# AS3364_DG412_bus_mixer_v1_1.net
KiCad netlist of a schematic drawn in EAGLE
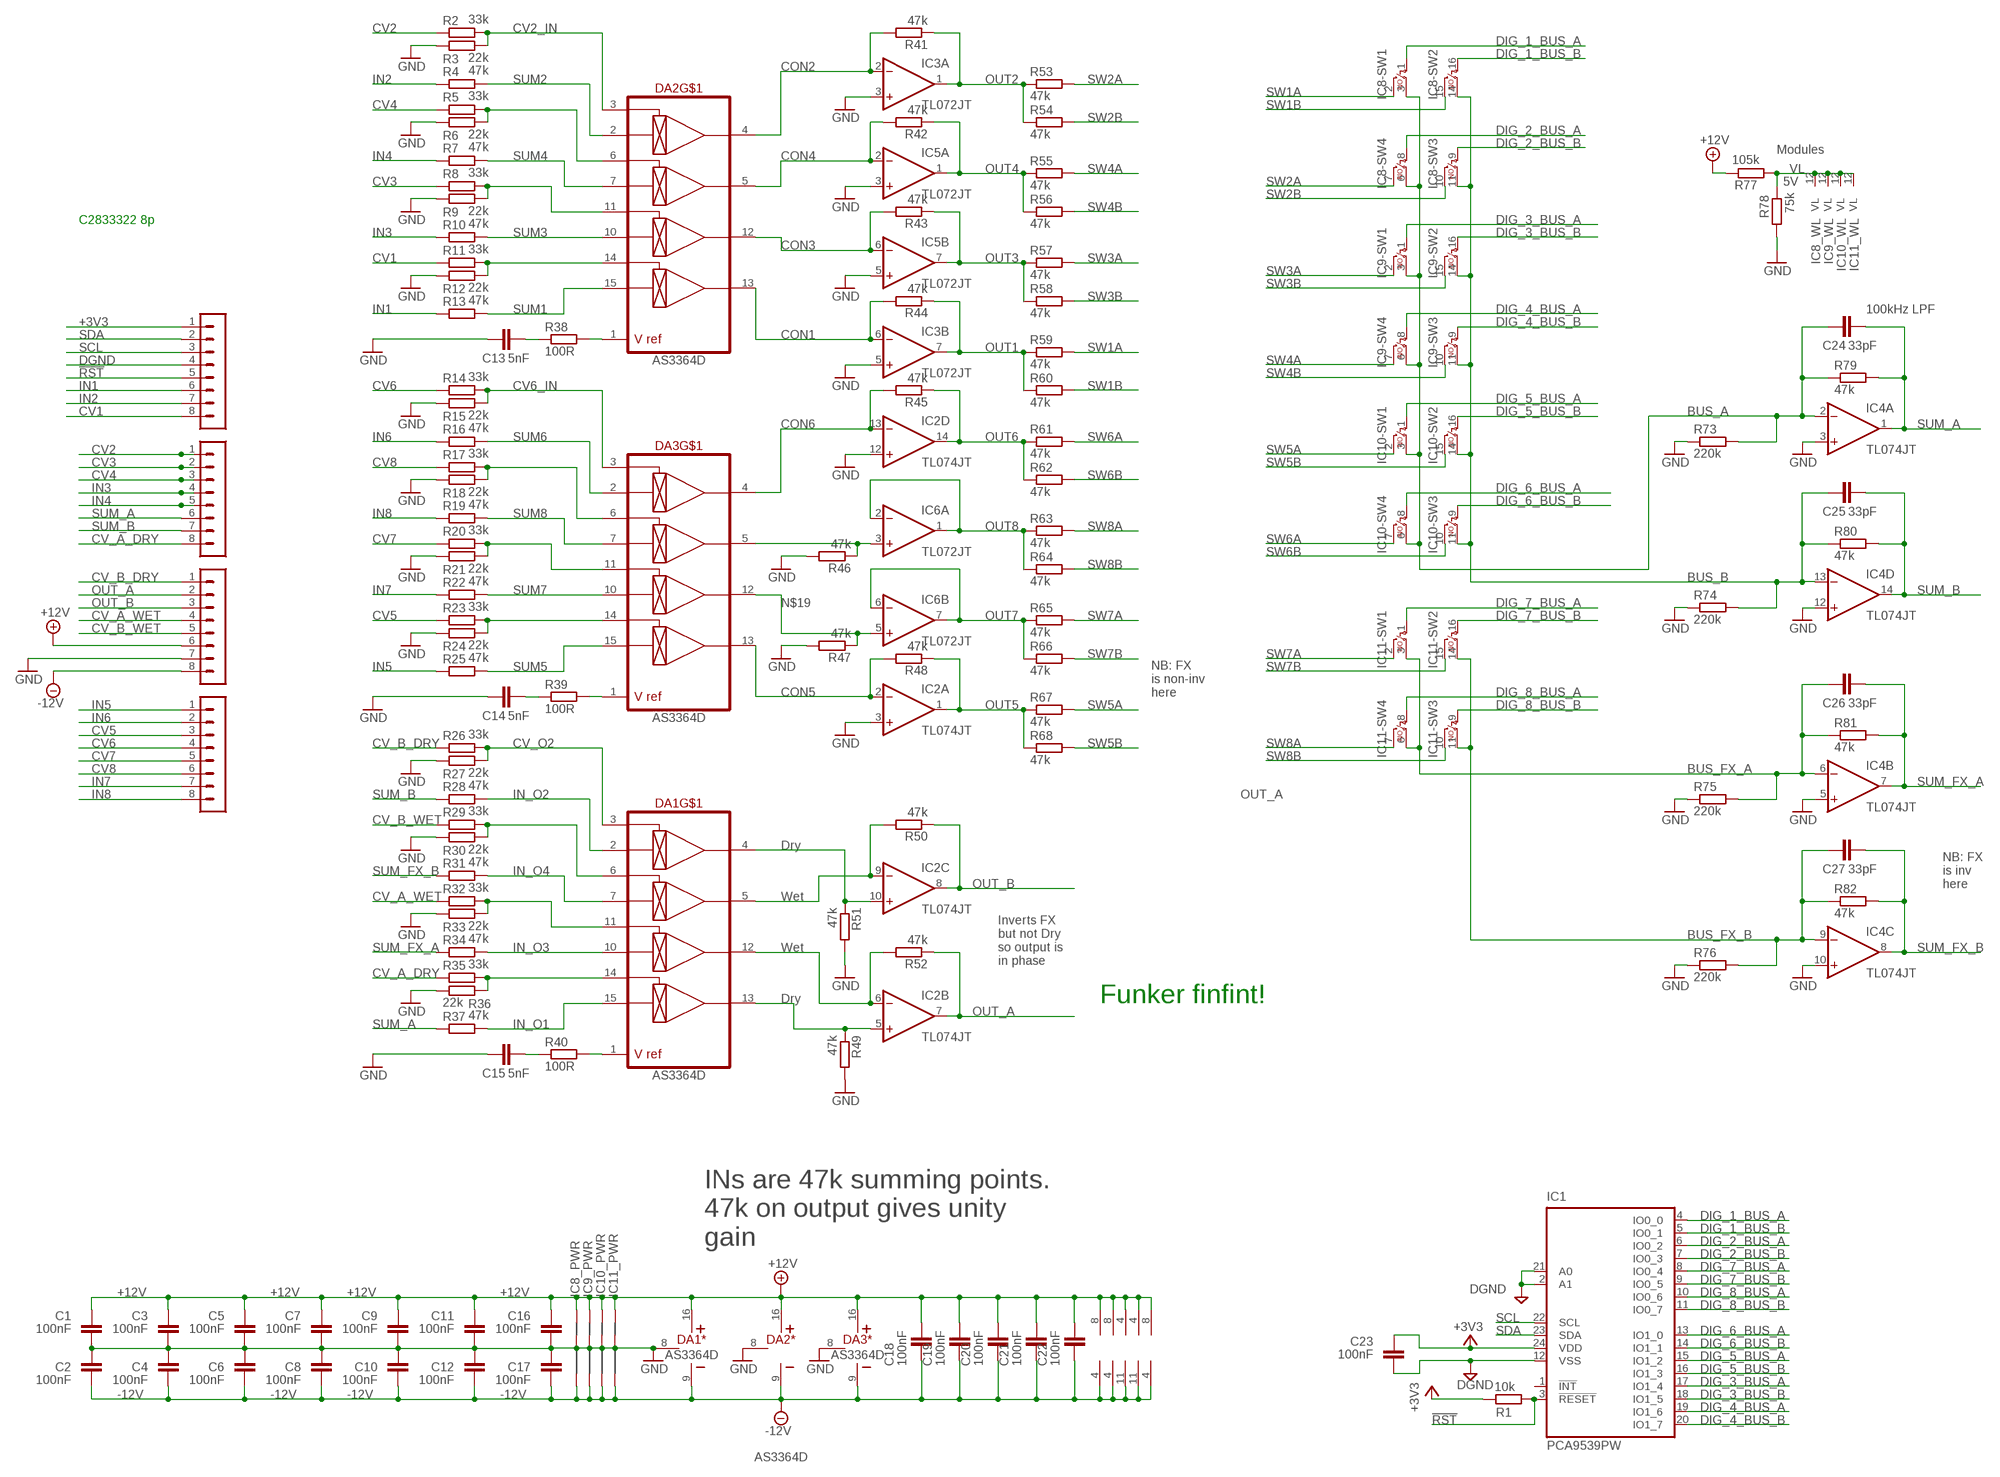
[diagram p0: schematic, sheet 1]

(export (version "E")
  (design (tool "Eeschema 10.0.6"))
  (components
    (comp (ref "C1")
      (value "100nF")
      (footprint "eagle-import:C0402")
      (libsource (lib "eagle-import") (part "C-EUC0402"))
    )
    (comp (ref "C2")
      (value "100nF")
      (footprint "eagle-import:C0402")
      (libsource (lib "eagle-import") (part "C-EUC0402"))
    )
    (comp (ref "C3")
      (value "100nF")
      (footprint "eagle-import:C0402")
      (libsource (lib "eagle-import") (part "C-EUC0402"))
    )
    (comp (ref "C4")
      (value "100nF")
      (footprint "eagle-import:C0402")
      (libsource (lib "eagle-import") (part "C-EUC0402"))
    )
    (comp (ref "C5")
      (value "100nF")
      (footprint "eagle-import:C0402")
      (libsource (lib "eagle-import") (part "C-EUC0402"))
    )
    (comp (ref "C6")
      (value "100nF")
      (footprint "eagle-import:C0402")
      (libsource (lib "eagle-import") (part "C-EUC0402"))
    )
    (comp (ref "C7")
      (value "100nF")
      (footprint "eagle-import:C0402")
      (libsource (lib "eagle-import") (part "C-EUC0402"))
    )
    (comp (ref "C8")
      (value "100nF")
      (footprint "eagle-import:C0402")
      (libsource (lib "eagle-import") (part "C-EUC0402"))
    )
    (comp (ref "C9")
      (value "100nF")
      (footprint "eagle-import:C0402")
      (libsource (lib "eagle-import") (part "C-EUC0402"))
    )
    (comp (ref "C10")
      (value "100nF")
      (footprint "eagle-import:C0402")
      (libsource (lib "eagle-import") (part "C-EUC0402"))
    )
    (comp (ref "C11")
      (value "100nF")
      (footprint "eagle-import:C0402")
      (libsource (lib "eagle-import") (part "C-EUC0402"))
    )
    (comp (ref "C12")
      (value "100nF")
      (footprint "eagle-import:C0402")
      (libsource (lib "eagle-import") (part "C-EUC0402"))
    )
    (comp (ref "C13")
      (value "5nF")
      (footprint "eagle-import:C0402-J")
      (libsource (lib "eagle-import") (part "C-EU-J"))
    )
    (comp (ref "C14")
      (value "5nF")
      (footprint "eagle-import:C0402-J")
      (libsource (lib "eagle-import") (part "C-EU-J"))
    )
    (comp (ref "C15")
      (value "5nF")
      (footprint "eagle-import:C0402-J")
      (libsource (lib "eagle-import") (part "C-EU-J"))
    )
    (comp (ref "C16")
      (value "100nF")
      (footprint "eagle-import:C0402")
      (libsource (lib "eagle-import") (part "C-EUC0402"))
    )
    (comp (ref "C17")
      (value "100nF")
      (footprint "eagle-import:C0402")
      (libsource (lib "eagle-import") (part "C-EUC0402"))
    )
    (comp (ref "C18")
      (value "100nF")
      (footprint "eagle-import:C0402")
      (libsource (lib "eagle-import") (part "C-EUC0402"))
    )
    (comp (ref "C19")
      (value "100nF")
      (footprint "eagle-import:C0402")
      (libsource (lib "eagle-import") (part "C-EUC0402"))
    )
    (comp (ref "C20")
      (value "100nF")
      (footprint "eagle-import:C0402")
      (libsource (lib "eagle-import") (part "C-EUC0402"))
    )
    (comp (ref "C21")
      (value "100nF")
      (footprint "eagle-import:C0402")
      (libsource (lib "eagle-import") (part "C-EUC0402"))
    )
    (comp (ref "C22")
      (value "100nF")
      (footprint "eagle-import:C0402")
      (libsource (lib "eagle-import") (part "C-EUC0402"))
    )
    (comp (ref "C23")
      (value "100nF")
      (footprint "eagle-import:C0402")
      (libsource (lib "eagle-import") (part "C-EUC0402"))
    )
    (comp (ref "C24")
      (value "33pF")
      (footprint "eagle-import:C0402-J")
      (libsource (lib "eagle-import") (part "C-EU-J"))
    )
    (comp (ref "C25")
      (value "33pF")
      (footprint "eagle-import:C0402-J")
      (libsource (lib "eagle-import") (part "C-EU-J"))
    )
    (comp (ref "C26")
      (value "33pF")
      (footprint "eagle-import:C0402-J")
      (libsource (lib "eagle-import") (part "C-EU-J"))
    )
    (comp (ref "C27")
      (value "33pF")
      (footprint "eagle-import:C0402-J")
      (libsource (lib "eagle-import") (part "C-EU-J"))
    )
    (comp (ref "DA1")
      (value "AS3364D")
      (footprint "eagle-import:DIL16J")
      (libsource (lib "eagle-import") (part "AS3364D"))
    )
    (comp (ref "DA2")
      (value "AS3364D")
      (footprint "eagle-import:DIL16J")
      (libsource (lib "eagle-import") (part "AS3364D"))
    )
    (comp (ref "DA3")
      (value "AS3364D")
      (footprint "eagle-import:DIL16J")
      (libsource (lib "eagle-import") (part "AS3364D"))
    )
    (comp (ref "IC1")
      (value "PCA9539PW")
      (footprint "eagle-import:TSSOP24J")
      (libsource (lib "eagle-import") (part "PCA9539PW"))
    )
    (comp (ref "IC2")
      (value "TL074JT")
      (footprint "eagle-import:TSSOP14J")
      (libsource (lib "eagle-import") (part "TL074JT"))
    )
    (comp (ref "IC3")
      (value "TL072JT")
      (footprint "eagle-import:TSSOP8J")
      (libsource (lib "eagle-import") (part "TL072JT"))
    )
    (comp (ref "IC4")
      (value "TL074JT")
      (footprint "eagle-import:TSSOP14J")
      (libsource (lib "eagle-import") (part "TL074JT"))
    )
    (comp (ref "IC5")
      (value "TL072JT")
      (footprint "eagle-import:TSSOP8J")
      (libsource (lib "eagle-import") (part "TL072JT"))
    )
    (comp (ref "IC6")
      (value "TL072JT")
      (footprint "eagle-import:TSSOP8J")
      (libsource (lib "eagle-import") (part "TL072JT"))
    )
    (comp (ref "IC8")
      (value "DG412-J")
      (footprint "eagle-import:DIL16J")
      (libsource (lib "eagle-import") (part "DG412-J"))
    )
    (comp (ref "IC9")
      (value "DG412-J")
      (footprint "eagle-import:DIL16J")
      (libsource (lib "eagle-import") (part "DG412-J"))
    )
    (comp (ref "IC10")
      (value "DG412-J")
      (footprint "eagle-import:DIL16J")
      (libsource (lib "eagle-import") (part "DG412-J"))
    )
    (comp (ref "IC11")
      (value "DG412-J")
      (footprint "eagle-import:DIL16J")
      (libsource (lib "eagle-import") (part "DG412-J"))
    )
    (comp (ref "R1")
      (value "10k")
      (footprint "eagle-import:R0402")
      (libsource (lib "eagle-import") (part "R-EU_R0402"))
    )
    (comp (ref "R2")
      (value "33k")
      (footprint "eagle-import:R0402")
      (libsource (lib "eagle-import") (part "R-EU_R0402"))
    )
    (comp (ref "R3")
      (value "22k")
      (footprint "eagle-import:R0402")
      (libsource (lib "eagle-import") (part "R-EU_R0402"))
    )
    (comp (ref "R4")
      (value "47k")
      (footprint "eagle-import:R0402")
      (libsource (lib "eagle-import") (part "R-EU_R0402"))
    )
    (comp (ref "R5")
      (value "33k")
      (footprint "eagle-import:R0402")
      (libsource (lib "eagle-import") (part "R-EU_R0402"))
    )
    (comp (ref "R6")
      (value "22k")
      (footprint "eagle-import:R0402")
      (libsource (lib "eagle-import") (part "R-EU_R0402"))
    )
    (comp (ref "R7")
      (value "47k")
      (footprint "eagle-import:R0402")
      (libsource (lib "eagle-import") (part "R-EU_R0402"))
    )
    (comp (ref "R8")
      (value "33k")
      (footprint "eagle-import:R0402")
      (libsource (lib "eagle-import") (part "R-EU_R0402"))
    )
    (comp (ref "R9")
      (value "22k")
      (footprint "eagle-import:R0402")
      (libsource (lib "eagle-import") (part "R-EU_R0402"))
    )
    (comp (ref "R10")
      (value "47k")
      (footprint "eagle-import:R0402")
      (libsource (lib "eagle-import") (part "R-EU_R0402"))
    )
    (comp (ref "R11")
      (value "33k")
      (footprint "eagle-import:R0402")
      (libsource (lib "eagle-import") (part "R-EU_R0402"))
    )
    (comp (ref "R12")
      (value "22k")
      (footprint "eagle-import:R0402")
      (libsource (lib "eagle-import") (part "R-EU_R0402"))
    )
    (comp (ref "R13")
      (value "47k")
      (footprint "eagle-import:R0402")
      (libsource (lib "eagle-import") (part "R-EU_R0402"))
    )
    (comp (ref "R14")
      (value "33k")
      (footprint "eagle-import:R0402")
      (libsource (lib "eagle-import") (part "R-EU_R0402"))
    )
    (comp (ref "R15")
      (value "22k")
      (footprint "eagle-import:R0402")
      (libsource (lib "eagle-import") (part "R-EU_R0402"))
    )
    (comp (ref "R16")
      (value "47k")
      (footprint "eagle-import:R0402")
      (libsource (lib "eagle-import") (part "R-EU_R0402"))
    )
    (comp (ref "R17")
      (value "33k")
      (footprint "eagle-import:R0402")
      (libsource (lib "eagle-import") (part "R-EU_R0402"))
    )
    (comp (ref "R18")
      (value "22k")
      (footprint "eagle-import:R0402")
      (libsource (lib "eagle-import") (part "R-EU_R0402"))
    )
    (comp (ref "R19")
      (value "47k")
      (footprint "eagle-import:R0402")
      (libsource (lib "eagle-import") (part "R-EU_R0402"))
    )
    (comp (ref "R20")
      (value "33k")
      (footprint "eagle-import:R0402")
      (libsource (lib "eagle-import") (part "R-EU_R0402"))
    )
    (comp (ref "R21")
      (value "22k")
      (footprint "eagle-import:R0402")
      (libsource (lib "eagle-import") (part "R-EU_R0402"))
    )
    (comp (ref "R22")
      (value "47k")
      (footprint "eagle-import:R0402")
      (libsource (lib "eagle-import") (part "R-EU_R0402"))
    )
    (comp (ref "R23")
      (value "33k")
      (footprint "eagle-import:R0402")
      (libsource (lib "eagle-import") (part "R-EU_R0402"))
    )
    (comp (ref "R24")
      (value "22k")
      (footprint "eagle-import:R0402")
      (libsource (lib "eagle-import") (part "R-EU_R0402"))
    )
    (comp (ref "R25")
      (value "47k")
      (footprint "eagle-import:R0402")
      (libsource (lib "eagle-import") (part "R-EU_R0402"))
    )
    (comp (ref "R26")
      (value "33k")
      (footprint "eagle-import:R0402")
      (libsource (lib "eagle-import") (part "R-EU_R0402"))
    )
    (comp (ref "R27")
      (value "22k")
      (footprint "eagle-import:R0402")
      (libsource (lib "eagle-import") (part "R-EU_R0402"))
    )
    (comp (ref "R28")
      (value "47k")
      (footprint "eagle-import:R0402")
      (libsource (lib "eagle-import") (part "R-EU_R0402"))
    )
    (comp (ref "R29")
      (value "33k")
      (footprint "eagle-import:R0402")
      (libsource (lib "eagle-import") (part "R-EU_R0402"))
    )
    (comp (ref "R30")
      (value "22k")
      (footprint "eagle-import:R0402")
      (libsource (lib "eagle-import") (part "R-EU_R0402"))
    )
    (comp (ref "R31")
      (value "47k")
      (footprint "eagle-import:R0402")
      (libsource (lib "eagle-import") (part "R-EU_R0402"))
    )
    (comp (ref "R32")
      (value "33k")
      (footprint "eagle-import:R0402")
      (libsource (lib "eagle-import") (part "R-EU_R0402"))
    )
    (comp (ref "R33")
      (value "22k")
      (footprint "eagle-import:R0402")
      (libsource (lib "eagle-import") (part "R-EU_R0402"))
    )
    (comp (ref "R34")
      (value "47k")
      (footprint "eagle-import:R0402")
      (libsource (lib "eagle-import") (part "R-EU_R0402"))
    )
    (comp (ref "R35")
      (value "33k")
      (footprint "eagle-import:R0402")
      (libsource (lib "eagle-import") (part "R-EU_R0402"))
    )
    (comp (ref "R36")
      (value "22k")
      (footprint "eagle-import:R0402")
      (libsource (lib "eagle-import") (part "R-EU_R0402"))
    )
    (comp (ref "R37")
      (value "47k")
      (footprint "eagle-import:R0402")
      (libsource (lib "eagle-import") (part "R-EU_R0402"))
    )
    (comp (ref "R38")
      (value "100R")
      (footprint "eagle-import:R0402")
      (libsource (lib "eagle-import") (part "R-EU_R0402"))
    )
    (comp (ref "R39")
      (value "100R")
      (footprint "eagle-import:R0402")
      (libsource (lib "eagle-import") (part "R-EU_R0402"))
    )
    (comp (ref "R40")
      (value "100R")
      (footprint "eagle-import:R0402")
      (libsource (lib "eagle-import") (part "R-EU_R0402"))
    )
    (comp (ref "R41")
      (value "47k")
      (footprint "eagle-import:R0402")
      (libsource (lib "eagle-import") (part "R-EU_R0402"))
    )
    (comp (ref "R42")
      (value "47k")
      (footprint "eagle-import:R0402")
      (libsource (lib "eagle-import") (part "R-EU_R0402"))
    )
    (comp (ref "R43")
      (value "47k")
      (footprint "eagle-import:R0402")
      (libsource (lib "eagle-import") (part "R-EU_R0402"))
    )
    (comp (ref "R44")
      (value "47k")
      (footprint "eagle-import:R0402")
      (libsource (lib "eagle-import") (part "R-EU_R0402"))
    )
    (comp (ref "R45")
      (value "47k")
      (footprint "eagle-import:R0402")
      (libsource (lib "eagle-import") (part "R-EU_R0402"))
    )
    (comp (ref "R46")
      (value "47k")
      (footprint "eagle-import:R0402")
      (libsource (lib "eagle-import") (part "R-EU_R0402"))
    )
    (comp (ref "R47")
      (value "47k")
      (footprint "eagle-import:R0402")
      (libsource (lib "eagle-import") (part "R-EU_R0402"))
    )
    (comp (ref "R48")
      (value "47k")
      (footprint "eagle-import:R0402")
      (libsource (lib "eagle-import") (part "R-EU_R0402"))
    )
    (comp (ref "R49")
      (value "47k")
      (footprint "eagle-import:R0402")
      (libsource (lib "eagle-import") (part "R-EU_R0402"))
    )
    (comp (ref "R50")
      (value "47k")
      (footprint "eagle-import:R0402")
      (libsource (lib "eagle-import") (part "R-EU_R0402"))
    )
    (comp (ref "R51")
      (value "47k")
      (footprint "eagle-import:R0402")
      (libsource (lib "eagle-import") (part "R-EU_R0402"))
    )
    (comp (ref "R52")
      (value "47k")
      (footprint "eagle-import:R0402")
      (libsource (lib "eagle-import") (part "R-EU_R0402"))
    )
    (comp (ref "R53")
      (value "47k")
      (footprint "eagle-import:R0402")
      (libsource (lib "eagle-import") (part "R-EU_R0402"))
    )
    (comp (ref "R54")
      (value "47k")
      (footprint "eagle-import:R0402")
      (libsource (lib "eagle-import") (part "R-EU_R0402"))
    )
    (comp (ref "R55")
      (value "47k")
      (footprint "eagle-import:R0402")
      (libsource (lib "eagle-import") (part "R-EU_R0402"))
    )
    (comp (ref "R56")
      (value "47k")
      (footprint "eagle-import:R0402")
      (libsource (lib "eagle-import") (part "R-EU_R0402"))
    )
    (comp (ref "R57")
      (value "47k")
      (footprint "eagle-import:R0402")
      (libsource (lib "eagle-import") (part "R-EU_R0402"))
    )
    (comp (ref "R58")
      (value "47k")
      (footprint "eagle-import:R0402")
      (libsource (lib "eagle-import") (part "R-EU_R0402"))
    )
    (comp (ref "R59")
      (value "47k")
      (footprint "eagle-import:R0402")
      (libsource (lib "eagle-import") (part "R-EU_R0402"))
    )
    (comp (ref "R60")
      (value "47k")
      (footprint "eagle-import:R0402")
      (libsource (lib "eagle-import") (part "R-EU_R0402"))
    )
    (comp (ref "R61")
      (value "47k")
      (footprint "eagle-import:R0402")
      (libsource (lib "eagle-import") (part "R-EU_R0402"))
    )
    (comp (ref "R62")
      (value "47k")
      (footprint "eagle-import:R0402")
      (libsource (lib "eagle-import") (part "R-EU_R0402"))
    )
    (comp (ref "R63")
      (value "47k")
      (footprint "eagle-import:R0402")
      (libsource (lib "eagle-import") (part "R-EU_R0402"))
    )
    (comp (ref "R64")
      (value "47k")
      (footprint "eagle-import:R0402")
      (libsource (lib "eagle-import") (part "R-EU_R0402"))
    )
    (comp (ref "R65")
      (value "47k")
      (footprint "eagle-import:R0402")
      (libsource (lib "eagle-import") (part "R-EU_R0402"))
    )
    (comp (ref "R66")
      (value "47k")
      (footprint "eagle-import:R0402")
      (libsource (lib "eagle-import") (part "R-EU_R0402"))
    )
    (comp (ref "R67")
      (value "47k")
      (footprint "eagle-import:R0402")
      (libsource (lib "eagle-import") (part "R-EU_R0402"))
    )
    (comp (ref "R68")
      (value "47k")
      (footprint "eagle-import:R0402")
      (libsource (lib "eagle-import") (part "R-EU_R0402"))
    )
    (comp (ref "R73")
      (value "220k")
      (footprint "eagle-import:R0402")
      (libsource (lib "eagle-import") (part "R-EU_R0402"))
    )
    (comp (ref "R74")
      (value "220k")
      (footprint "eagle-import:R0402")
      (libsource (lib "eagle-import") (part "R-EU_R0402"))
    )
    (comp (ref "R75")
      (value "220k")
      (footprint "eagle-import:R0402")
      (libsource (lib "eagle-import") (part "R-EU_R0402"))
    )
    (comp (ref "R76")
      (value "220k")
      (footprint "eagle-import:R0402")
      (libsource (lib "eagle-import") (part "R-EU_R0402"))
    )
    (comp (ref "R77")
      (value "105k")
      (footprint "eagle-import:R0402")
      (libsource (lib "eagle-import") (part "R-EU_R0402"))
    )
    (comp (ref "R78")
      (value "75k")
      (footprint "eagle-import:R0402")
      (libsource (lib "eagle-import") (part "R-EU_R0402"))
    )
    (comp (ref "R79")
      (value "47k")
      (footprint "eagle-import:R0402")
      (libsource (lib "eagle-import") (part "R-EU_R0402"))
    )
    (comp (ref "R80")
      (value "47k")
      (footprint "eagle-import:R0402")
      (libsource (lib "eagle-import") (part "R-EU_R0402"))
    )
    (comp (ref "R81")
      (value "47k")
      (footprint "eagle-import:R0402")
      (libsource (lib "eagle-import") (part "R-EU_R0402"))
    )
    (comp (ref "R82")
      (value "47k")
      (footprint "eagle-import:R0402")
      (libsource (lib "eagle-import") (part "R-EU_R0402"))
    )
    (comp (ref "SV1")
      (value "MA08-1JP")
      (footprint "eagle-import:SIP-PIN08-1J")
      (libsource (lib "eagle-import") (part "MA08-1JP"))
    )
    (comp (ref "SV3")
      (value "MA08-1JP")
      (footprint "eagle-import:SIP-PIN08-1J")
      (libsource (lib "eagle-import") (part "MA08-1JP"))
    )
    (comp (ref "SV4")
      (value "MA08-1JP")
      (footprint "eagle-import:SIP-PIN08-1J")
      (libsource (lib "eagle-import") (part "MA08-1JP"))
    )
    (comp (ref "SV33")
      (value "MA08-1JP")
      (footprint "eagle-import:SIP-PIN08-1J")
      (libsource (lib "eagle-import") (part "MA08-1JP"))
    )
  )
  (nets
    (net (code "1") (name "+3V3") (class "Default")
      (node (ref "C23") (pin "2") (pinfunction "2_2") (pintype "passive"))
      (node (ref "IC1") (pin "24") (pinfunction "VDD_24") (pintype "power_in"))
      (node (ref "R1") (pin "1") (pinfunction "1_1") (pintype "passive"))
      (node (ref "SV33") (pin "1") (pinfunction "1_1") (pintype "passive"))
    )
    (net (code "2") (name "+12V") (class "Default")
      (node (ref "C1") (pin "2") (pinfunction "2_2") (pintype "passive"))
      (node (ref "C11") (pin "2") (pinfunction "2_2") (pintype "passive"))
      (node (ref "C16") (pin "2") (pinfunction "2_2") (pintype "passive"))
      (node (ref "C18") (pin "2") (pinfunction "2_2") (pintype "passive"))
      (node (ref "C19") (pin "2") (pinfunction "2_2") (pintype "passive"))
      (node (ref "C20") (pin "2") (pinfunction "2_2") (pintype "passive"))
      (node (ref "C21") (pin "2") (pinfunction "2_2") (pintype "passive"))
      (node (ref "C22") (pin "2") (pinfunction "2_2") (pintype "passive"))
      (node (ref "C3") (pin "2") (pinfunction "2_2") (pintype "passive"))
      (node (ref "C5") (pin "2") (pinfunction "2_2") (pintype "passive"))
      (node (ref "C7") (pin "2") (pinfunction "2_2") (pintype "passive"))
      (node (ref "C9") (pin "2") (pinfunction "2_2") (pintype "passive"))
      (node (ref "DA1") (pin "16") (pinfunction "V+_16") (pintype "power_in"))
      (node (ref "DA2") (pin "16") (pinfunction "V+_16") (pintype "power_in"))
      (node (ref "DA3") (pin "16") (pinfunction "V+_16") (pintype "power_in"))
      (node (ref "IC10") (pin "13") (pinfunction "+15V_13") (pintype "power_in"))
      (node (ref "IC11") (pin "13") (pinfunction "+15V_13") (pintype "power_in"))
      (node (ref "IC2") (pin "4") (pinfunction "V+_4") (pintype "power_in"))
      (node (ref "IC3") (pin "8") (pinfunction "V+_8") (pintype "power_in"))
      (node (ref "IC4") (pin "4") (pinfunction "V+_4") (pintype "power_in"))
      (node (ref "IC5") (pin "8") (pinfunction "V+_8") (pintype "power_in"))
      (node (ref "IC6") (pin "8") (pinfunction "V+_8") (pintype "power_in"))
      (node (ref "IC8") (pin "13") (pinfunction "+15V_13") (pintype "power_in"))
      (node (ref "IC9") (pin "13") (pinfunction "+15V_13") (pintype "power_in"))
      (node (ref "R77") (pin "1") (pinfunction "1_1") (pintype "passive"))
      (node (ref "SV4") (pin "6") (pinfunction "6_6") (pintype "passive"))
    )
    (net (code "3") (name "-12V") (class "Default")
      (node (ref "C10") (pin "1") (pinfunction "1_1") (pintype "passive"))
      (node (ref "C12") (pin "1") (pinfunction "1_1") (pintype "passive"))
      (node (ref "C17") (pin "1") (pinfunction "1_1") (pintype "passive"))
      (node (ref "C18") (pin "1") (pinfunction "1_1") (pintype "passive"))
      (node (ref "C19") (pin "1") (pinfunction "1_1") (pintype "passive"))
      (node (ref "C2") (pin "1") (pinfunction "1_1") (pintype "passive"))
      (node (ref "C20") (pin "1") (pinfunction "1_1") (pintype "passive"))
      (node (ref "C21") (pin "1") (pinfunction "1_1") (pintype "passive"))
      (node (ref "C22") (pin "1") (pinfunction "1_1") (pintype "passive"))
      (node (ref "C4") (pin "1") (pinfunction "1_1") (pintype "passive"))
      (node (ref "C6") (pin "1") (pinfunction "1_1") (pintype "passive"))
      (node (ref "C8") (pin "1") (pinfunction "1_1") (pintype "passive"))
      (node (ref "DA1") (pin "9") (pinfunction "V-_9") (pintype "power_in"))
      (node (ref "DA2") (pin "9") (pinfunction "V-_9") (pintype "power_in"))
      (node (ref "DA3") (pin "9") (pinfunction "V-_9") (pintype "power_in"))
      (node (ref "IC10") (pin "4") (pinfunction "-15V_4") (pintype "power_in"))
      (node (ref "IC11") (pin "4") (pinfunction "-15V_4") (pintype "power_in"))
      (node (ref "IC2") (pin "11") (pinfunction "V-_11") (pintype "power_in"))
      (node (ref "IC3") (pin "4") (pinfunction "V-_4") (pintype "power_in"))
      (node (ref "IC4") (pin "11") (pinfunction "V-_11") (pintype "power_in"))
      (node (ref "IC5") (pin "4") (pinfunction "V-_4") (pintype "power_in"))
      (node (ref "IC6") (pin "4") (pinfunction "V-_4") (pintype "power_in"))
      (node (ref "IC8") (pin "4") (pinfunction "-15V_4") (pintype "power_in"))
      (node (ref "IC9") (pin "4") (pinfunction "-15V_4") (pintype "power_in"))
      (node (ref "SV4") (pin "8") (pinfunction "8_8") (pintype "passive"))
    )
    (net (code "4") (name "/BUS_A") (class "Default")
      (node (ref "C24") (pin "1") (pinfunction "1_1") (pintype "passive"))
      (node (ref "IC10") (pin "3") (pinfunction "S_3") (pintype "bidirectional"))
      (node (ref "IC10") (pin "6") (pinfunction "S_6") (pintype "bidirectional"))
      (node (ref "IC4") (pin "2") (pinfunction "-IN_2") (pintype "input"))
      (node (ref "IC8") (pin "3") (pinfunction "S_3") (pintype "bidirectional"))
      (node (ref "IC8") (pin "6") (pinfunction "S_6") (pintype "bidirectional"))
      (node (ref "IC9") (pin "3") (pinfunction "S_3") (pintype "bidirectional"))
      (node (ref "IC9") (pin "6") (pinfunction "S_6") (pintype "bidirectional"))
      (node (ref "R73") (pin "2") (pinfunction "2_2") (pintype "passive"))
      (node (ref "R79") (pin "1") (pinfunction "1_1") (pintype "passive"))
    )
    (net (code "5") (name "/BUS_B") (class "Default")
      (node (ref "C25") (pin "1") (pinfunction "1_1") (pintype "passive"))
      (node (ref "IC10") (pin "11") (pinfunction "S_11") (pintype "bidirectional"))
      (node (ref "IC10") (pin "14") (pinfunction "S_14") (pintype "bidirectional"))
      (node (ref "IC4") (pin "13") (pinfunction "-IN_13") (pintype "input"))
      (node (ref "IC8") (pin "11") (pinfunction "S_11") (pintype "bidirectional"))
      (node (ref "IC8") (pin "14") (pinfunction "S_14") (pintype "bidirectional"))
      (node (ref "IC9") (pin "11") (pinfunction "S_11") (pintype "bidirectional"))
      (node (ref "IC9") (pin "14") (pinfunction "S_14") (pintype "bidirectional"))
      (node (ref "R74") (pin "2") (pinfunction "2_2") (pintype "passive"))
      (node (ref "R80") (pin "1") (pinfunction "1_1") (pintype "passive"))
    )
    (net (code "6") (name "/BUS_FX_A") (class "Default")
      (node (ref "C26") (pin "1") (pinfunction "1_1") (pintype "passive"))
      (node (ref "IC11") (pin "3") (pinfunction "S_3") (pintype "bidirectional"))
      (node (ref "IC11") (pin "6") (pinfunction "S_6") (pintype "bidirectional"))
      (node (ref "IC4") (pin "6") (pinfunction "-IN_6") (pintype "input"))
      (node (ref "R75") (pin "2") (pinfunction "2_2") (pintype "passive"))
      (node (ref "R81") (pin "1") (pinfunction "1_1") (pintype "passive"))
    )
    (net (code "7") (name "/BUS_FX_B") (class "Default")
      (node (ref "C27") (pin "1") (pinfunction "1_1") (pintype "passive"))
      (node (ref "IC11") (pin "11") (pinfunction "S_11") (pintype "bidirectional"))
      (node (ref "IC11") (pin "14") (pinfunction "S_14") (pintype "bidirectional"))
      (node (ref "IC4") (pin "9") (pinfunction "-IN_9") (pintype "input"))
      (node (ref "R76") (pin "2") (pinfunction "2_2") (pintype "passive"))
      (node (ref "R82") (pin "1") (pinfunction "1_1") (pintype "passive"))
    )
    (net (code "8") (name "/CON1") (class "Default")
      (node (ref "DA2") (pin "13") (pinfunction "OUT4_13") (pintype "output"))
      (node (ref "IC3") (pin "6") (pinfunction "-IN_6") (pintype "input"))
      (node (ref "R44") (pin "2") (pinfunction "2_2") (pintype "passive"))
    )
    (net (code "9") (name "/CON2") (class "Default")
      (node (ref "DA2") (pin "4") (pinfunction "OUT1_4") (pintype "output"))
      (node (ref "IC3") (pin "2") (pinfunction "-IN_2") (pintype "input"))
      (node (ref "R41") (pin "2") (pinfunction "2_2") (pintype "passive"))
    )
    (net (code "10") (name "/CON3") (class "Default")
      (node (ref "DA2") (pin "12") (pinfunction "OUT3_12") (pintype "output"))
      (node (ref "IC5") (pin "6") (pinfunction "-IN_6") (pintype "input"))
      (node (ref "R43") (pin "2") (pinfunction "2_2") (pintype "passive"))
    )
    (net (code "11") (name "/CON4") (class "Default")
      (node (ref "DA2") (pin "5") (pinfunction "OUT2_5") (pintype "output"))
      (node (ref "IC5") (pin "2") (pinfunction "-IN_2") (pintype "input"))
      (node (ref "R42") (pin "2") (pinfunction "2_2") (pintype "passive"))
    )
    (net (code "12") (name "/CON5") (class "Default")
      (node (ref "DA3") (pin "13") (pinfunction "OUT4_13") (pintype "output"))
      (node (ref "IC2") (pin "2") (pinfunction "-IN_2") (pintype "input"))
      (node (ref "R48") (pin "2") (pinfunction "2_2") (pintype "passive"))
    )
    (net (code "13") (name "/CON6") (class "Default")
      (node (ref "DA3") (pin "4") (pinfunction "OUT1_4") (pintype "output"))
      (node (ref "IC2") (pin "13") (pinfunction "-IN_13") (pintype "input"))
      (node (ref "R45") (pin "2") (pinfunction "2_2") (pintype "passive"))
    )
    (net (code "14") (name "/CV1") (class "Default")
      (node (ref "R11") (pin "1") (pinfunction "1_1") (pintype "passive"))
      (node (ref "SV33") (pin "8") (pinfunction "8_8") (pintype "passive"))
    )
    (net (code "15") (name "/CV2") (class "Default")
      (node (ref "R2") (pin "1") (pinfunction "1_1") (pintype "passive"))
      (node (ref "SV1") (pin "1") (pinfunction "1_1") (pintype "passive"))
    )
    (net (code "16") (name "/CV2_IN") (class "Default")
      (node (ref "DA2") (pin "3") (pinfunction "CV1_3") (pintype "input"))
      (node (ref "R2") (pin "2") (pinfunction "2_2") (pintype "passive"))
      (node (ref "R3") (pin "2") (pinfunction "2_2") (pintype "passive"))
    )
    (net (code "17") (name "/CV3") (class "Default")
      (node (ref "R8") (pin "1") (pinfunction "1_1") (pintype "passive"))
      (node (ref "SV1") (pin "2") (pinfunction "2_2") (pintype "passive"))
    )
    (net (code "18") (name "/CV4") (class "Default")
      (node (ref "R5") (pin "1") (pinfunction "1_1") (pintype "passive"))
      (node (ref "SV1") (pin "3") (pinfunction "3_3") (pintype "passive"))
    )
    (net (code "19") (name "/CV5") (class "Default")
      (node (ref "R23") (pin "1") (pinfunction "1_1") (pintype "passive"))
      (node (ref "SV3") (pin "3") (pinfunction "3_3") (pintype "passive"))
    )
    (net (code "20") (name "/CV6") (class "Default")
      (node (ref "R14") (pin "1") (pinfunction "1_1") (pintype "passive"))
      (node (ref "SV3") (pin "4") (pinfunction "4_4") (pintype "passive"))
    )
    (net (code "21") (name "/CV6_IN") (class "Default")
      (node (ref "DA3") (pin "3") (pinfunction "CV1_3") (pintype "input"))
      (node (ref "R14") (pin "2") (pinfunction "2_2") (pintype "passive"))
      (node (ref "R15") (pin "2") (pinfunction "2_2") (pintype "passive"))
    )
    (net (code "22") (name "/CV7") (class "Default")
      (node (ref "R20") (pin "1") (pinfunction "1_1") (pintype "passive"))
      (node (ref "SV3") (pin "5") (pinfunction "5_5") (pintype "passive"))
    )
    (net (code "23") (name "/CV8") (class "Default")
      (node (ref "R17") (pin "1") (pinfunction "1_1") (pintype "passive"))
      (node (ref "SV3") (pin "6") (pinfunction "6_6") (pintype "passive"))
    )
    (net (code "24") (name "/CV_A_DRY") (class "Default")
      (node (ref "R35") (pin "1") (pinfunction "1_1") (pintype "passive"))
      (node (ref "SV1") (pin "8") (pinfunction "8_8") (pintype "passive"))
    )
    (net (code "25") (name "/CV_A_WET") (class "Default")
      (node (ref "R32") (pin "1") (pinfunction "1_1") (pintype "passive"))
      (node (ref "SV4") (pin "4") (pinfunction "4_4") (pintype "passive"))
    )
    (net (code "26") (name "/CV_B_DRY") (class "Default")
      (node (ref "R26") (pin "1") (pinfunction "1_1") (pintype "passive"))
      (node (ref "SV4") (pin "1") (pinfunction "1_1") (pintype "passive"))
    )
    (net (code "27") (name "/CV_B_WET") (class "Default")
      (node (ref "R29") (pin "1") (pinfunction "1_1") (pintype "passive"))
      (node (ref "SV4") (pin "5") (pinfunction "5_5") (pintype "passive"))
    )
    (net (code "28") (name "/CV_O2") (class "Default")
      (node (ref "DA1") (pin "3") (pinfunction "CV1_3") (pintype "input"))
      (node (ref "R26") (pin "2") (pinfunction "2_2") (pintype "passive"))
      (node (ref "R27") (pin "2") (pinfunction "2_2") (pintype "passive"))
    )
    (net (code "29") (name "/DIG_1_BUS_A") (class "Default")
      (node (ref "IC1") (pin "4") (pinfunction "IO0_0_4") (pintype "bidirectional"))
      (node (ref "IC8") (pin "1") (pinfunction "C_1") (pintype "bidirectional"))
    )
    (net (code "30") (name "/DIG_1_BUS_B") (class "Default")
      (node (ref "IC1") (pin "5") (pinfunction "IO0_1_5") (pintype "bidirectional"))
      (node (ref "IC8") (pin "16") (pinfunction "C_16") (pintype "bidirectional"))
    )
    (net (code "31") (name "/DIG_2_BUS_A") (class "Default")
      (node (ref "IC1") (pin "6") (pinfunction "IO0_2_6") (pintype "bidirectional"))
      (node (ref "IC8") (pin "8") (pinfunction "C_8") (pintype "bidirectional"))
    )
    (net (code "32") (name "/DIG_2_BUS_B") (class "Default")
      (node (ref "IC1") (pin "7") (pinfunction "IO0_3_7") (pintype "bidirectional"))
      (node (ref "IC8") (pin "9") (pinfunction "C_9") (pintype "bidirectional"))
    )
    (net (code "33") (name "/DIG_3_BUS_A") (class "Default")
      (node (ref "IC1") (pin "17") (pinfunction "IO1_4_17") (pintype "bidirectional"))
      (node (ref "IC9") (pin "1") (pinfunction "C_1") (pintype "bidirectional"))
    )
    (net (code "34") (name "/DIG_3_BUS_B") (class "Default")
      (node (ref "IC1") (pin "18") (pinfunction "IO1_5_18") (pintype "bidirectional"))
      (node (ref "IC9") (pin "16") (pinfunction "C_16") (pintype "bidirectional"))
    )
    (net (code "35") (name "/DIG_4_BUS_A") (class "Default")
      (node (ref "IC1") (pin "19") (pinfunction "IO1_6_19") (pintype "bidirectional"))
      (node (ref "IC9") (pin "8") (pinfunction "C_8") (pintype "bidirectional"))
    )
    (net (code "36") (name "/DIG_4_BUS_B") (class "Default")
      (node (ref "IC1") (pin "20") (pinfunction "IO1_7_20") (pintype "bidirectional"))
      (node (ref "IC9") (pin "9") (pinfunction "C_9") (pintype "bidirectional"))
    )
    (net (code "37") (name "/DIG_5_BUS_A") (class "Default")
      (node (ref "IC1") (pin "15") (pinfunction "IO1_2_15") (pintype "bidirectional"))
      (node (ref "IC10") (pin "1") (pinfunction "C_1") (pintype "bidirectional"))
    )
    (net (code "38") (name "/DIG_5_BUS_B") (class "Default")
      (node (ref "IC1") (pin "16") (pinfunction "IO1_3_16") (pintype "bidirectional"))
      (node (ref "IC10") (pin "16") (pinfunction "C_16") (pintype "bidirectional"))
    )
    (net (code "39") (name "/DIG_6_BUS_A") (class "Default")
      (node (ref "IC1") (pin "13") (pinfunction "IO1_0_13") (pintype "bidirectional"))
      (node (ref "IC10") (pin "8") (pinfunction "C_8") (pintype "bidirectional"))
    )
    (net (code "40") (name "/DIG_6_BUS_B") (class "Default")
      (node (ref "IC1") (pin "14") (pinfunction "IO1_1_14") (pintype "bidirectional"))
      (node (ref "IC10") (pin "9") (pinfunction "C_9") (pintype "bidirectional"))
    )
    (net (code "41") (name "/DIG_7_BUS_A") (class "Default")
      (node (ref "IC1") (pin "8") (pinfunction "IO0_4_8") (pintype "bidirectional"))
      (node (ref "IC11") (pin "1") (pinfunction "C_1") (pintype "bidirectional"))
    )
    (net (code "42") (name "/DIG_7_BUS_B") (class "Default")
      (node (ref "IC1") (pin "9") (pinfunction "IO0_5_9") (pintype "bidirectional"))
      (node (ref "IC11") (pin "16") (pinfunction "C_16") (pintype "bidirectional"))
    )
    (net (code "43") (name "/DIG_8_BUS_A") (class "Default")
      (node (ref "IC1") (pin "10") (pinfunction "IO0_6_10") (pintype "bidirectional"))
      (node (ref "IC11") (pin "8") (pinfunction "C_8") (pintype "bidirectional"))
    )
    (net (code "44") (name "/DIG_8_BUS_B") (class "Default")
      (node (ref "IC1") (pin "11") (pinfunction "IO0_7_11") (pintype "bidirectional"))
      (node (ref "IC11") (pin "9") (pinfunction "C_9") (pintype "bidirectional"))
    )
    (net (code "45") (name "/IN1") (class "Default")
      (node (ref "R13") (pin "1") (pinfunction "1_1") (pintype "passive"))
      (node (ref "SV33") (pin "6") (pinfunction "6_6") (pintype "passive"))
    )
    (net (code "46") (name "/IN2") (class "Default")
      (node (ref "R4") (pin "1") (pinfunction "1_1") (pintype "passive"))
      (node (ref "SV33") (pin "7") (pinfunction "7_7") (pintype "passive"))
    )
    (net (code "47") (name "/IN3") (class "Default")
      (node (ref "R10") (pin "1") (pinfunction "1_1") (pintype "passive"))
      (node (ref "SV1") (pin "4") (pinfunction "4_4") (pintype "passive"))
    )
    (net (code "48") (name "/IN4") (class "Default")
      (node (ref "R7") (pin "1") (pinfunction "1_1") (pintype "passive"))
      (node (ref "SV1") (pin "5") (pinfunction "5_5") (pintype "passive"))
    )
    (net (code "49") (name "/IN5") (class "Default")
      (node (ref "R25") (pin "1") (pinfunction "1_1") (pintype "passive"))
      (node (ref "SV3") (pin "1") (pinfunction "1_1") (pintype "passive"))
    )
    (net (code "50") (name "/IN6") (class "Default")
      (node (ref "R16") (pin "1") (pinfunction "1_1") (pintype "passive"))
      (node (ref "SV3") (pin "2") (pinfunction "2_2") (pintype "passive"))
    )
    (net (code "51") (name "/IN7") (class "Default")
      (node (ref "R22") (pin "1") (pinfunction "1_1") (pintype "passive"))
      (node (ref "SV3") (pin "7") (pinfunction "7_7") (pintype "passive"))
    )
    (net (code "52") (name "/IN8") (class "Default")
      (node (ref "R19") (pin "1") (pinfunction "1_1") (pintype "passive"))
      (node (ref "SV3") (pin "8") (pinfunction "8_8") (pintype "passive"))
    )
    (net (code "53") (name "/IN_O1") (class "Default")
      (node (ref "DA1") (pin "15") (pinfunction "IN4_15") (pintype "input"))
      (node (ref "R37") (pin "2") (pinfunction "2_2") (pintype "passive"))
    )
    (net (code "54") (name "/IN_O2") (class "Default")
      (node (ref "DA1") (pin "2") (pinfunction "IN1_2") (pintype "input"))
      (node (ref "R28") (pin "2") (pinfunction "2_2") (pintype "passive"))
    )
    (net (code "55") (name "/IN_O3") (class "Default")
      (node (ref "DA1") (pin "10") (pinfunction "IN3_10") (pintype "input"))
      (node (ref "R34") (pin "2") (pinfunction "2_2") (pintype "passive"))
    )
    (net (code "56") (name "/IN_O4") (class "Default")
      (node (ref "DA1") (pin "7") (pinfunction "IN2_7") (pintype "input"))
      (node (ref "R31") (pin "2") (pinfunction "2_2") (pintype "passive"))
    )
    (net (code "57") (name "/N$19") (class "Default")
      (node (ref "DA3") (pin "12") (pinfunction "OUT3_12") (pintype "output"))
      (node (ref "IC6") (pin "5") (pinfunction "+IN_5") (pintype "input"))
      (node (ref "R47") (pin "1") (pinfunction "1_1") (pintype "passive"))
    )
    (net (code "58") (name "/OUT1") (class "Default")
      (node (ref "IC3") (pin "7") (pinfunction "OUT_7") (pintype "output"))
      (node (ref "R44") (pin "1") (pinfunction "1_1") (pintype "passive"))
      (node (ref "R59") (pin "1") (pinfunction "1_1") (pintype "passive"))
      (node (ref "R60") (pin "1") (pinfunction "1_1") (pintype "passive"))
    )
    (net (code "59") (name "/OUT2") (class "Default")
      (node (ref "IC3") (pin "1") (pinfunction "OUT_1") (pintype "output"))
      (node (ref "R41") (pin "1") (pinfunction "1_1") (pintype "passive"))
      (node (ref "R53") (pin "1") (pinfunction "1_1") (pintype "passive"))
      (node (ref "R54") (pin "1") (pinfunction "1_1") (pintype "passive"))
    )
    (net (code "60") (name "/OUT3") (class "Default")
      (node (ref "IC5") (pin "7") (pinfunction "OUT_7") (pintype "output"))
      (node (ref "R43") (pin "1") (pinfunction "1_1") (pintype "passive"))
      (node (ref "R57") (pin "1") (pinfunction "1_1") (pintype "passive"))
      (node (ref "R58") (pin "1") (pinfunction "1_1") (pintype "passive"))
    )
    (net (code "61") (name "/OUT4") (class "Default")
      (node (ref "IC5") (pin "1") (pinfunction "OUT_1") (pintype "output"))
      (node (ref "R42") (pin "1") (pinfunction "1_1") (pintype "passive"))
      (node (ref "R55") (pin "1") (pinfunction "1_1") (pintype "passive"))
      (node (ref "R56") (pin "1") (pinfunction "1_1") (pintype "passive"))
    )
    (net (code "62") (name "/OUT5") (class "Default")
      (node (ref "IC2") (pin "1") (pinfunction "OUT_1") (pintype "output"))
      (node (ref "R48") (pin "1") (pinfunction "1_1") (pintype "passive"))
      (node (ref "R67") (pin "1") (pinfunction "1_1") (pintype "passive"))
      (node (ref "R68") (pin "1") (pinfunction "1_1") (pintype "passive"))
    )
    (net (code "63") (name "/OUT6") (class "Default")
      (node (ref "IC2") (pin "14") (pinfunction "OUT_14") (pintype "output"))
      (node (ref "R45") (pin "1") (pinfunction "1_1") (pintype "passive"))
      (node (ref "R61") (pin "1") (pinfunction "1_1") (pintype "passive"))
      (node (ref "R62") (pin "1") (pinfunction "1_1") (pintype "passive"))
    )
    (net (code "64") (name "/OUT7") (class "Default")
      (node (ref "IC6") (pin "6") (pinfunction "-IN_6") (pintype "input"))
      (node (ref "IC6") (pin "7") (pinfunction "OUT_7") (pintype "output"))
      (node (ref "R65") (pin "1") (pinfunction "1_1") (pintype "passive"))
      (node (ref "R66") (pin "1") (pinfunction "1_1") (pintype "passive"))
    )
    (net (code "65") (name "/OUT8") (class "Default")
      (node (ref "IC6") (pin "1") (pinfunction "OUT_1") (pintype "output"))
      (node (ref "IC6") (pin "2") (pinfunction "-IN_2") (pintype "input"))
      (node (ref "R63") (pin "1") (pinfunction "1_1") (pintype "passive"))
      (node (ref "R64") (pin "1") (pinfunction "1_1") (pintype "passive"))
    )
    (net (code "66") (name "/OUT_A") (class "Default")
      (node (ref "IC2") (pin "7") (pinfunction "OUT_7") (pintype "output"))
      (node (ref "R52") (pin "1") (pinfunction "1_1") (pintype "passive"))
      (node (ref "SV4") (pin "2") (pinfunction "2_2") (pintype "passive"))
    )
    (net (code "67") (name "/OUT_B") (class "Default")
      (node (ref "IC2") (pin "8") (pinfunction "OUT_8") (pintype "output"))
      (node (ref "R50") (pin "1") (pinfunction "1_1") (pintype "passive"))
      (node (ref "SV4") (pin "3") (pinfunction "3_3") (pintype "passive"))
    )
    (net (code "68") (name "/SCL") (class "Default")
      (node (ref "IC1") (pin "22") (pinfunction "SCL_22") (pintype "bidirectional"))
      (node (ref "SV33") (pin "3") (pinfunction "3_3") (pintype "passive"))
    )
    (net (code "69") (name "/SDA") (class "Default")
      (node (ref "IC1") (pin "23") (pinfunction "SDA_23") (pintype "bidirectional"))
      (node (ref "SV33") (pin "2") (pinfunction "2_2") (pintype "passive"))
    )
    (net (code "70") (name "/SUM1") (class "Default")
      (node (ref "DA2") (pin "15") (pinfunction "IN4_15") (pintype "input"))
      (node (ref "R13") (pin "2") (pinfunction "2_2") (pintype "passive"))
    )
    (net (code "71") (name "/SUM2") (class "Default")
      (node (ref "DA2") (pin "2") (pinfunction "IN1_2") (pintype "input"))
      (node (ref "R4") (pin "2") (pinfunction "2_2") (pintype "passive"))
    )
    (net (code "72") (name "/SUM3") (class "Default")
      (node (ref "DA2") (pin "10") (pinfunction "IN3_10") (pintype "input"))
      (node (ref "R10") (pin "2") (pinfunction "2_2") (pintype "passive"))
    )
    (net (code "73") (name "/SUM4") (class "Default")
      (node (ref "DA2") (pin "7") (pinfunction "IN2_7") (pintype "input"))
      (node (ref "R7") (pin "2") (pinfunction "2_2") (pintype "passive"))
    )
    (net (code "74") (name "/SUM5") (class "Default")
      (node (ref "DA3") (pin "15") (pinfunction "IN4_15") (pintype "input"))
      (node (ref "R25") (pin "2") (pinfunction "2_2") (pintype "passive"))
    )
    (net (code "75") (name "/SUM6") (class "Default")
      (node (ref "DA3") (pin "2") (pinfunction "IN1_2") (pintype "input"))
      (node (ref "R16") (pin "2") (pinfunction "2_2") (pintype "passive"))
    )
    (net (code "76") (name "/SUM7") (class "Default")
      (node (ref "DA3") (pin "10") (pinfunction "IN3_10") (pintype "input"))
      (node (ref "R22") (pin "2") (pinfunction "2_2") (pintype "passive"))
    )
    (net (code "77") (name "/SUM8") (class "Default")
      (node (ref "DA3") (pin "7") (pinfunction "IN2_7") (pintype "input"))
      (node (ref "R19") (pin "2") (pinfunction "2_2") (pintype "passive"))
    )
    (net (code "78") (name "/SUM_A") (class "Default")
      (node (ref "C24") (pin "2") (pinfunction "2_2") (pintype "passive"))
      (node (ref "IC4") (pin "1") (pinfunction "OUT_1") (pintype "output"))
      (node (ref "R37") (pin "1") (pinfunction "1_1") (pintype "passive"))
      (node (ref "R79") (pin "2") (pinfunction "2_2") (pintype "passive"))
      (node (ref "SV1") (pin "6") (pinfunction "6_6") (pintype "passive"))
    )
    (net (code "79") (name "/SUM_B") (class "Default")
      (node (ref "C25") (pin "2") (pinfunction "2_2") (pintype "passive"))
      (node (ref "IC4") (pin "14") (pinfunction "OUT_14") (pintype "output"))
      (node (ref "R28") (pin "1") (pinfunction "1_1") (pintype "passive"))
      (node (ref "R80") (pin "2") (pinfunction "2_2") (pintype "passive"))
      (node (ref "SV1") (pin "7") (pinfunction "7_7") (pintype "passive"))
    )
    (net (code "80") (name "/SUM_FX_A") (class "Default")
      (node (ref "C26") (pin "2") (pinfunction "2_2") (pintype "passive"))
      (node (ref "IC4") (pin "7") (pinfunction "OUT_7") (pintype "output"))
      (node (ref "R34") (pin "1") (pinfunction "1_1") (pintype "passive"))
      (node (ref "R81") (pin "2") (pinfunction "2_2") (pintype "passive"))
    )
    (net (code "81") (name "/SUM_FX_B") (class "Default")
      (node (ref "C27") (pin "2") (pinfunction "2_2") (pintype "passive"))
      (node (ref "IC4") (pin "8") (pinfunction "OUT_8") (pintype "output"))
      (node (ref "R31") (pin "1") (pinfunction "1_1") (pintype "passive"))
      (node (ref "R82") (pin "2") (pinfunction "2_2") (pintype "passive"))
    )
    (net (code "82") (name "/SW1A") (class "Default")
      (node (ref "IC8") (pin "2") (pinfunction "D_2") (pintype "bidirectional"))
      (node (ref "R59") (pin "2") (pinfunction "2_2") (pintype "passive"))
    )
    (net (code "83") (name "/SW1B") (class "Default")
      (node (ref "IC8") (pin "15") (pinfunction "D_15") (pintype "bidirectional"))
      (node (ref "R60") (pin "2") (pinfunction "2_2") (pintype "passive"))
    )
    (net (code "84") (name "/SW2A") (class "Default")
      (node (ref "IC8") (pin "7") (pinfunction "D_7") (pintype "bidirectional"))
      (node (ref "R53") (pin "2") (pinfunction "2_2") (pintype "passive"))
    )
    (net (code "85") (name "/SW2B") (class "Default")
      (node (ref "IC8") (pin "10") (pinfunction "D_10") (pintype "bidirectional"))
      (node (ref "R54") (pin "2") (pinfunction "2_2") (pintype "passive"))
    )
    (net (code "86") (name "/SW3A") (class "Default")
      (node (ref "IC9") (pin "2") (pinfunction "D_2") (pintype "bidirectional"))
      (node (ref "R57") (pin "2") (pinfunction "2_2") (pintype "passive"))
    )
    (net (code "87") (name "/SW3B") (class "Default")
      (node (ref "IC9") (pin "15") (pinfunction "D_15") (pintype "bidirectional"))
      (node (ref "R58") (pin "2") (pinfunction "2_2") (pintype "passive"))
    )
    (net (code "88") (name "/SW4A") (class "Default")
      (node (ref "IC9") (pin "7") (pinfunction "D_7") (pintype "bidirectional"))
      (node (ref "R55") (pin "2") (pinfunction "2_2") (pintype "passive"))
    )
    (net (code "89") (name "/SW4B") (class "Default")
      (node (ref "IC9") (pin "10") (pinfunction "D_10") (pintype "bidirectional"))
      (node (ref "R56") (pin "2") (pinfunction "2_2") (pintype "passive"))
    )
    (net (code "90") (name "/SW5A") (class "Default")
      (node (ref "IC10") (pin "2") (pinfunction "D_2") (pintype "bidirectional"))
      (node (ref "R67") (pin "2") (pinfunction "2_2") (pintype "passive"))
    )
    (net (code "91") (name "/SW5B") (class "Default")
      (node (ref "IC10") (pin "15") (pinfunction "D_15") (pintype "bidirectional"))
      (node (ref "R68") (pin "2") (pinfunction "2_2") (pintype "passive"))
    )
    (net (code "92") (name "/SW6A") (class "Default")
      (node (ref "IC10") (pin "7") (pinfunction "D_7") (pintype "bidirectional"))
      (node (ref "R61") (pin "2") (pinfunction "2_2") (pintype "passive"))
    )
    (net (code "93") (name "/SW6B") (class "Default")
      (node (ref "IC10") (pin "10") (pinfunction "D_10") (pintype "bidirectional"))
      (node (ref "R62") (pin "2") (pinfunction "2_2") (pintype "passive"))
    )
    (net (code "94") (name "/SW7A") (class "Default")
      (node (ref "IC11") (pin "2") (pinfunction "D_2") (pintype "bidirectional"))
      (node (ref "R65") (pin "2") (pinfunction "2_2") (pintype "passive"))
    )
    (net (code "95") (name "/SW7B") (class "Default")
      (node (ref "IC11") (pin "15") (pinfunction "D_15") (pintype "bidirectional"))
      (node (ref "R66") (pin "2") (pinfunction "2_2") (pintype "passive"))
    )
    (net (code "96") (name "/SW8A") (class "Default")
      (node (ref "IC11") (pin "7") (pinfunction "D_7") (pintype "bidirectional"))
      (node (ref "R63") (pin "2") (pinfunction "2_2") (pintype "passive"))
    )
    (net (code "97") (name "/SW8B") (class "Default")
      (node (ref "IC11") (pin "10") (pinfunction "D_10") (pintype "bidirectional"))
      (node (ref "R64") (pin "2") (pinfunction "2_2") (pintype "passive"))
    )
    (net (code "98") (name "/VL") (class "Default")
      (node (ref "IC10") (pin "12") (pinfunction "VL_12") (pintype "bidirectional"))
      (node (ref "IC11") (pin "12") (pinfunction "VL_12") (pintype "bidirectional"))
      (node (ref "IC8") (pin "12") (pinfunction "VL_12") (pintype "bidirectional"))
      (node (ref "IC9") (pin "12") (pinfunction "VL_12") (pintype "bidirectional"))
      (node (ref "R77") (pin "2") (pinfunction "2_2") (pintype "passive"))
      (node (ref "R78") (pin "1") (pinfunction "1_1") (pintype "passive"))
    )
    (net (code "99") (name "/~{RST}") (class "Default")
      (node (ref "IC1") (pin "3") (pinfunction "~{RESET}_3") (pintype "bidirectional"))
      (node (ref "R1") (pin "2") (pinfunction "2_2") (pintype "passive"))
      (node (ref "SV33") (pin "5") (pinfunction "5_5") (pintype "passive"))
    )
    (net (code "100") (name "DGND") (class "Default")
      (node (ref "C23") (pin "1") (pinfunction "1_1") (pintype "passive"))
      (node (ref "IC1") (pin "12") (pinfunction "VSS_12") (pintype "power_in"))
      (node (ref "IC1") (pin "2") (pinfunction "A1_2") (pintype "bidirectional"))
      (node (ref "IC1") (pin "21") (pinfunction "A0_21") (pintype "bidirectional"))
      (node (ref "SV33") (pin "4") (pinfunction "4_4") (pintype "passive"))
    )
    (net (code "101") (name "GND") (class "Default")
      (node (ref "C1") (pin "1") (pinfunction "1_1") (pintype "passive"))
      (node (ref "C10") (pin "2") (pinfunction "2_2") (pintype "passive"))
      (node (ref "C11") (pin "1") (pinfunction "1_1") (pintype "passive"))
      (node (ref "C12") (pin "2") (pinfunction "2_2") (pintype "passive"))
      (node (ref "C13") (pin "1") (pinfunction "1_1") (pintype "passive"))
      (node (ref "C14") (pin "1") (pinfunction "1_1") (pintype "passive"))
      (node (ref "C15") (pin "1") (pinfunction "1_1") (pintype "passive"))
      (node (ref "C16") (pin "1") (pinfunction "1_1") (pintype "passive"))
      (node (ref "C17") (pin "2") (pinfunction "2_2") (pintype "passive"))
      (node (ref "C2") (pin "2") (pinfunction "2_2") (pintype "passive"))
      (node (ref "C3") (pin "1") (pinfunction "1_1") (pintype "passive"))
      (node (ref "C4") (pin "2") (pinfunction "2_2") (pintype "passive"))
      (node (ref "C5") (pin "1") (pinfunction "1_1") (pintype "passive"))
      (node (ref "C6") (pin "2") (pinfunction "2_2") (pintype "passive"))
      (node (ref "C7") (pin "1") (pinfunction "1_1") (pintype "passive"))
      (node (ref "C8") (pin "2") (pinfunction "2_2") (pintype "passive"))
      (node (ref "C9") (pin "1") (pinfunction "1_1") (pintype "passive"))
      (node (ref "DA1") (pin "8") (pinfunction "GND_8") (pintype "power_in"))
      (node (ref "DA2") (pin "8") (pinfunction "GND_8") (pintype "power_in"))
      (node (ref "DA3") (pin "8") (pinfunction "GND_8") (pintype "power_in"))
      (node (ref "IC10") (pin "5") (pinfunction "AGND_5") (pintype "power_in"))
      (node (ref "IC11") (pin "5") (pinfunction "AGND_5") (pintype "power_in"))
      (node (ref "IC2") (pin "12") (pinfunction "+IN_12") (pintype "input"))
      (node (ref "IC2") (pin "3") (pinfunction "+IN_3") (pintype "input"))
      (node (ref "IC3") (pin "3") (pinfunction "+IN_3") (pintype "input"))
      (node (ref "IC3") (pin "5") (pinfunction "+IN_5") (pintype "input"))
      (node (ref "IC4") (pin "10") (pinfunction "+IN_10") (pintype "input"))
      (node (ref "IC4") (pin "12") (pinfunction "+IN_12") (pintype "input"))
      (node (ref "IC4") (pin "3") (pinfunction "+IN_3") (pintype "input"))
      (node (ref "IC4") (pin "5") (pinfunction "+IN_5") (pintype "input"))
      (node (ref "IC5") (pin "3") (pinfunction "+IN_3") (pintype "input"))
      (node (ref "IC5") (pin "5") (pinfunction "+IN_5") (pintype "input"))
      (node (ref "IC8") (pin "5") (pinfunction "AGND_5") (pintype "power_in"))
      (node (ref "IC9") (pin "5") (pinfunction "AGND_5") (pintype "power_in"))
      (node (ref "R12") (pin "1") (pinfunction "1_1") (pintype "passive"))
      (node (ref "R15") (pin "1") (pinfunction "1_1") (pintype "passive"))
      (node (ref "R18") (pin "1") (pinfunction "1_1") (pintype "passive"))
      (node (ref "R21") (pin "1") (pinfunction "1_1") (pintype "passive"))
      (node (ref "R24") (pin "1") (pinfunction "1_1") (pintype "passive"))
      (node (ref "R27") (pin "1") (pinfunction "1_1") (pintype "passive"))
      (node (ref "R3") (pin "1") (pinfunction "1_1") (pintype "passive"))
      (node (ref "R30") (pin "1") (pinfunction "1_1") (pintype "passive"))
      (node (ref "R33") (pin "1") (pinfunction "1_1") (pintype "passive"))
      (node (ref "R36") (pin "1") (pinfunction "1_1") (pintype "passive"))
      (node (ref "R46") (pin "2") (pinfunction "2_2") (pintype "passive"))
      (node (ref "R47") (pin "2") (pinfunction "2_2") (pintype "passive"))
      (node (ref "R49") (pin "2") (pinfunction "2_2") (pintype "passive"))
      (node (ref "R51") (pin "2") (pinfunction "2_2") (pintype "passive"))
      (node (ref "R6") (pin "1") (pinfunction "1_1") (pintype "passive"))
      (node (ref "R73") (pin "1") (pinfunction "1_1") (pintype "passive"))
      (node (ref "R74") (pin "1") (pinfunction "1_1") (pintype "passive"))
      (node (ref "R75") (pin "1") (pinfunction "1_1") (pintype "passive"))
      (node (ref "R76") (pin "1") (pinfunction "1_1") (pintype "passive"))
      (node (ref "R78") (pin "2") (pinfunction "2_2") (pintype "passive"))
      (node (ref "R9") (pin "1") (pinfunction "1_1") (pintype "passive"))
      (node (ref "SV4") (pin "7") (pinfunction "7_7") (pintype "passive"))
    )
    (net (code "102") (name "Net-(C13-Pad2)") (class "Default")
      (node (ref "C13") (pin "2") (pinfunction "2_2") (pintype "passive"))
      (node (ref "R38") (pin "1") (pinfunction "1_1") (pintype "passive"))
    )
    (net (code "103") (name "Net-(C14-Pad2)") (class "Default")
      (node (ref "C14") (pin "2") (pinfunction "2_2") (pintype "passive"))
      (node (ref "R39") (pin "1") (pinfunction "1_1") (pintype "passive"))
    )
    (net (code "104") (name "Net-(C15-Pad2)") (class "Default")
      (node (ref "C15") (pin "2") (pinfunction "2_2") (pintype "passive"))
      (node (ref "R40") (pin "1") (pinfunction "1_1") (pintype "passive"))
    )
    (net (code "105") (name "Net-(DA1B-CV2)") (class "Default")
      (node (ref "DA1") (pin "6") (pinfunction "CV2_6") (pintype "input"))
      (node (ref "R29") (pin "2") (pinfunction "2_2") (pintype "passive"))
      (node (ref "R30") (pin "2") (pinfunction "2_2") (pintype "passive"))
    )
    (net (code "106") (name "Net-(DA1B-CV3)") (class "Default")
      (node (ref "DA1") (pin "11") (pinfunction "CV3_11") (pintype "input"))
      (node (ref "R32") (pin "2") (pinfunction "2_2") (pintype "passive"))
      (node (ref "R33") (pin "2") (pinfunction "2_2") (pintype "passive"))
    )
    (net (code "107") (name "Net-(DA1B-CV4)") (class "Default")
      (node (ref "DA1") (pin "14") (pinfunction "CV4_14") (pintype "input"))
      (node (ref "R35") (pin "2") (pinfunction "2_2") (pintype "passive"))
      (node (ref "R36") (pin "2") (pinfunction "2_2") (pintype "passive"))
    )
    (net (code "108") (name "Net-(DA1B-OUT1)") (class "Default")
      (node (ref "DA1") (pin "4") (pinfunction "OUT1_4") (pintype "output"))
      (node (ref "IC2") (pin "10") (pinfunction "+IN_10") (pintype "input"))
      (node (ref "R51") (pin "1") (pinfunction "1_1") (pintype "passive"))
    )
    (net (code "109") (name "Net-(DA1B-OUT2)") (class "Default")
      (node (ref "DA1") (pin "5") (pinfunction "OUT2_5") (pintype "output"))
      (node (ref "IC2") (pin "9") (pinfunction "-IN_9") (pintype "input"))
      (node (ref "R50") (pin "2") (pinfunction "2_2") (pintype "passive"))
    )
    (net (code "110") (name "Net-(DA1B-OUT3)") (class "Default")
      (node (ref "DA1") (pin "12") (pinfunction "OUT3_12") (pintype "output"))
      (node (ref "IC2") (pin "6") (pinfunction "-IN_6") (pintype "input"))
      (node (ref "R52") (pin "2") (pinfunction "2_2") (pintype "passive"))
    )
    (net (code "111") (name "Net-(DA1B-OUT4)") (class "Default")
      (node (ref "DA1") (pin "13") (pinfunction "OUT4_13") (pintype "output"))
      (node (ref "IC2") (pin "5") (pinfunction "+IN_5") (pintype "input"))
      (node (ref "R49") (pin "1") (pinfunction "1_1") (pintype "passive"))
    )
    (net (code "112") (name "Net-(DA1B-VREF)") (class "Default")
      (node (ref "DA1") (pin "1") (pinfunction "VREF_1") (pintype "output"))
      (node (ref "R40") (pin "2") (pinfunction "2_2") (pintype "passive"))
    )
    (net (code "113") (name "Net-(DA2B-CV2)") (class "Default")
      (node (ref "DA2") (pin "6") (pinfunction "CV2_6") (pintype "input"))
      (node (ref "R5") (pin "2") (pinfunction "2_2") (pintype "passive"))
      (node (ref "R6") (pin "2") (pinfunction "2_2") (pintype "passive"))
    )
    (net (code "114") (name "Net-(DA2B-CV3)") (class "Default")
      (node (ref "DA2") (pin "11") (pinfunction "CV3_11") (pintype "input"))
      (node (ref "R8") (pin "2") (pinfunction "2_2") (pintype "passive"))
      (node (ref "R9") (pin "2") (pinfunction "2_2") (pintype "passive"))
    )
    (net (code "115") (name "Net-(DA2B-CV4)") (class "Default")
      (node (ref "DA2") (pin "14") (pinfunction "CV4_14") (pintype "input"))
      (node (ref "R11") (pin "2") (pinfunction "2_2") (pintype "passive"))
      (node (ref "R12") (pin "2") (pinfunction "2_2") (pintype "passive"))
    )
    (net (code "116") (name "Net-(DA2B-VREF)") (class "Default")
      (node (ref "DA2") (pin "1") (pinfunction "VREF_1") (pintype "output"))
      (node (ref "R38") (pin "2") (pinfunction "2_2") (pintype "passive"))
    )
    (net (code "117") (name "Net-(DA3B-CV2)") (class "Default")
      (node (ref "DA3") (pin "6") (pinfunction "CV2_6") (pintype "input"))
      (node (ref "R17") (pin "2") (pinfunction "2_2") (pintype "passive"))
      (node (ref "R18") (pin "2") (pinfunction "2_2") (pintype "passive"))
    )
    (net (code "118") (name "Net-(DA3B-CV3)") (class "Default")
      (node (ref "DA3") (pin "11") (pinfunction "CV3_11") (pintype "input"))
      (node (ref "R20") (pin "2") (pinfunction "2_2") (pintype "passive"))
      (node (ref "R21") (pin "2") (pinfunction "2_2") (pintype "passive"))
    )
    (net (code "119") (name "Net-(DA3B-CV4)") (class "Default")
      (node (ref "DA3") (pin "14") (pinfunction "CV4_14") (pintype "input"))
      (node (ref "R23") (pin "2") (pinfunction "2_2") (pintype "passive"))
      (node (ref "R24") (pin "2") (pinfunction "2_2") (pintype "passive"))
    )
    (net (code "120") (name "Net-(DA3B-OUT2)") (class "Default")
      (node (ref "DA3") (pin "5") (pinfunction "OUT2_5") (pintype "output"))
      (node (ref "IC6") (pin "3") (pinfunction "+IN_3") (pintype "input"))
      (node (ref "R46") (pin "1") (pinfunction "1_1") (pintype "passive"))
    )
    (net (code "121") (name "Net-(DA3B-VREF)") (class "Default")
      (node (ref "DA3") (pin "1") (pinfunction "VREF_1") (pintype "output"))
      (node (ref "R39") (pin "2") (pinfunction "2_2") (pintype "passive"))
    )
    (net (code "122") (name "unconnected-(IC1-~{INT}-Pad1)") (class "Default")
      (node (ref "IC1") (pin "1") (pinfunction "~{INT}_1") (pintype "bidirectional"))
    )
  )
)
